# PulT.net
KiCad netlist of a schematic drawn in EAGLE
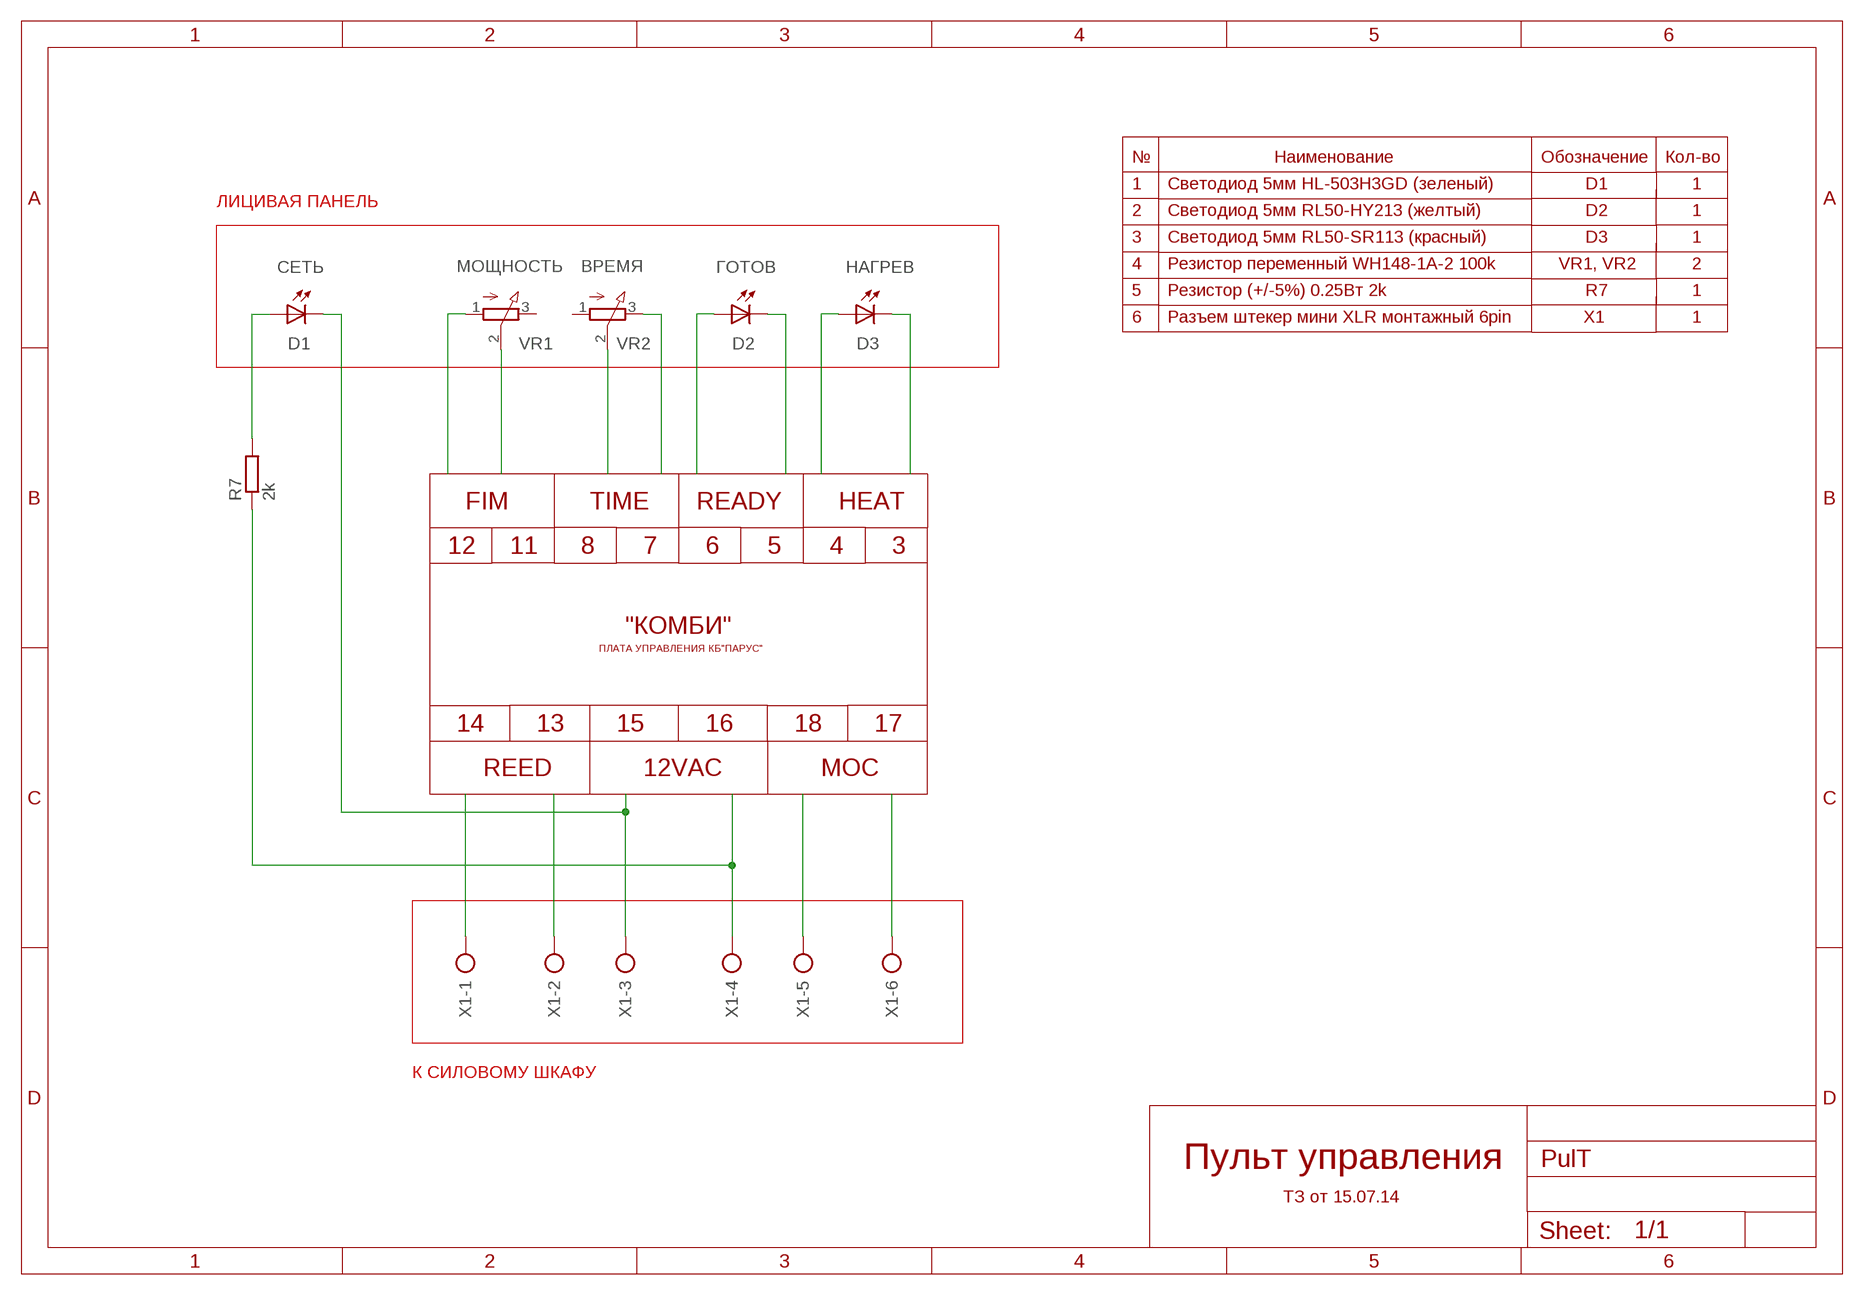
[diagram p0: schematic, sheet 1]

(export (version "E")
  (design (tool "Eeschema 10.0.6"))
  (components
    (comp (ref "R7")
      (value "2k")
      (footprint "eagle-import:0207_5V")
      (libsource (lib "eagle-import") (part "R-EU_0207/5V"))
    )
    (comp (ref "X1")
      (value "AK500/6")
      (footprint "eagle-import:AK500_6")
      (libsource (lib "eagle-import") (part "AK500/6"))
    )
    (comp (ref "ВРЕМЯ")
      (value "3RP/1610N")
      (footprint "eagle-import:3RP_1610N")
      (libsource (lib "eagle-import") (part "3RP/1610N"))
    )
    (comp (ref "ГОТОВ")
      (value "LED5MM")
      (footprint "eagle-import:LED5MM")
      (libsource (lib "eagle-import") (part "LED5MM"))
    )
    (comp (ref "МОЩНОСТЬ")
      (value "3RP/1610N")
      (footprint "eagle-import:3RP_1610N")
      (libsource (lib "eagle-import") (part "3RP/1610N"))
    )
    (comp (ref "НАГРЕВ")
      (value "LED5MM")
      (footprint "eagle-import:LED5MM")
      (libsource (lib "eagle-import") (part "LED5MM"))
    )
    (comp (ref "СЕТЬ")
      (value "LED5MM")
      (footprint "eagle-import:LED5MM")
      (libsource (lib "eagle-import") (part "LED5MM"))
    )
  )
  (nets
    (net (code "1") (name "Net-(R7-Pad2)") (class "Default")
      (node (ref "R7") (pin "2") (pinfunction "2_2") (pintype "passive"))
      (node (ref "СЕТЬ") (pin "A") (pinfunction "A_A") (pintype "passive"))
    )
    (net (code "2") (name "Net-(X1C-KL)") (class "Default")
      (node (ref "X1") (pin "3") (pinfunction "KL_3") (pintype "passive"))
      (node (ref "СЕТЬ") (pin "K") (pinfunction "C_K") (pintype "passive"))
    )
    (net (code "3") (name "Net-(X1D-KL)") (class "Default")
      (node (ref "R7") (pin "1") (pinfunction "1_1") (pintype "passive"))
      (node (ref "X1") (pin "4") (pinfunction "KL_4") (pintype "passive"))
    )
    (net (code "4") (name "unconnected-(X1A-KL-Pad1)") (class "Default")
      (node (ref "X1") (pin "1") (pinfunction "KL_1") (pintype "passive"))
    )
    (net (code "5") (name "unconnected-(X1B-KL-Pad2)") (class "Default")
      (node (ref "X1") (pin "2") (pinfunction "KL_2") (pintype "passive"))
    )
    (net (code "6") (name "unconnected-(X1E-KL-Pad5)") (class "Default")
      (node (ref "X1") (pin "5") (pinfunction "KL_5") (pintype "passive"))
    )
    (net (code "7") (name "unconnected-(X1F-KL-Pad6)") (class "Default")
      (node (ref "X1") (pin "6") (pinfunction "KL_6") (pintype "passive"))
    )
    (net (code "8") (name "unconnected-(ВРЕМЯ-A-Pad1)") (class "Default")
      (node (ref "ВРЕМЯ") (pin "1") (pinfunction "A_1") (pintype "passive"))
    )
    (net (code "9") (name "unconnected-(ВРЕМЯ-E-Pad3)") (class "Default")
      (node (ref "ВРЕМЯ") (pin "3") (pinfunction "E_3") (pintype "passive"))
    )
    (net (code "10") (name "unconnected-(ВРЕМЯ-S-Pad2)") (class "Default")
      (node (ref "ВРЕМЯ") (pin "2") (pinfunction "S_2") (pintype "passive"))
    )
    (net (code "11") (name "unconnected-(ГОТОВ-C-PadK)") (class "Default")
      (node (ref "ГОТОВ") (pin "K") (pinfunction "C_K") (pintype "passive"))
    )
    (net (code "12") (name "unconnected-(ГОТОВ-PadA)") (class "Default")
      (node (ref "ГОТОВ") (pin "A") (pinfunction "A_A") (pintype "passive"))
    )
    (net (code "13") (name "unconnected-(МОЩНОСТЬ-A-Pad1)") (class "Default")
      (node (ref "МОЩНОСТЬ") (pin "1") (pinfunction "A_1") (pintype "passive"))
    )
    (net (code "14") (name "unconnected-(МОЩНОСТЬ-E-Pad3)") (class "Default")
      (node (ref "МОЩНОСТЬ") (pin "3") (pinfunction "E_3") (pintype "passive"))
    )
    (net (code "15") (name "unconnected-(МОЩНОСТЬ-S-Pad2)") (class "Default")
      (node (ref "МОЩНОСТЬ") (pin "2") (pinfunction "S_2") (pintype "passive"))
    )
    (net (code "16") (name "unconnected-(НАГРЕВ-C-PadK)") (class "Default")
      (node (ref "НАГРЕВ") (pin "K") (pinfunction "C_K") (pintype "passive"))
    )
    (net (code "17") (name "unconnected-(НАГРЕВ-PadA)") (class "Default")
      (node (ref "НАГРЕВ") (pin "A") (pinfunction "A_A") (pintype "passive"))
    )
  )
)
